# Debugging.net
KiCad netlist of a schematic drawn in Altium Designer
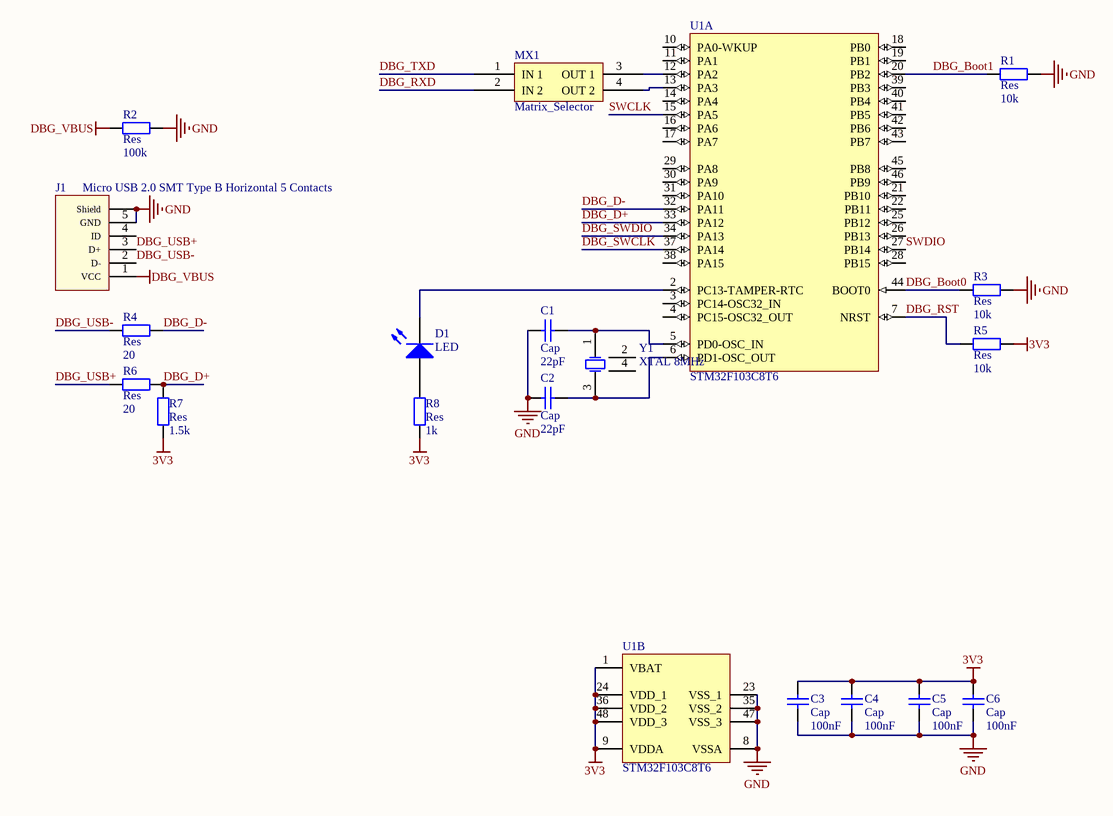
[diagram p0: Debugging.SchDoc]

(export (version "E")
  (design (tool "Eeschema 10.0.6"))
  (components
    (comp (ref "C1")
      (value "Cap")
      (footprint "C0603")
      (description "Capacitor")
      (fields (field (name "ALTIUM_VALUE") "22pF") (field (name "PUBLISHER") "Altium Limited"))
      (libsource (lib "cadLib") (part "Cap"))
    )
    (comp (ref "C2")
      (value "Cap")
      (footprint "C0603")
      (description "Capacitor")
      (fields (field (name "ALTIUM_VALUE") "22pF") (field (name "PUBLISHER") "Altium Limited"))
      (libsource (lib "cadLib") (part "Cap"))
    )
    (comp (ref "C3")
      (value "Cap")
      (footprint "C0603")
      (description "Capacitor")
      (fields (field (name "ALTIUM_VALUE") "100nF") (field (name "PUBLISHER") "Altium Limited"))
      (libsource (lib "cadLib") (part "Cap"))
    )
    (comp (ref "C4")
      (value "Cap")
      (footprint "C0603")
      (description "Capacitor")
      (fields (field (name "ALTIUM_VALUE") "100nF") (field (name "PUBLISHER") "Altium Limited"))
      (libsource (lib "cadLib") (part "Cap"))
    )
    (comp (ref "C5")
      (value "Cap")
      (footprint "C0603")
      (description "Capacitor")
      (fields (field (name "ALTIUM_VALUE") "100nF") (field (name "PUBLISHER") "Altium Limited"))
      (libsource (lib "cadLib") (part "Cap"))
    )
    (comp (ref "C6")
      (value "Cap")
      (footprint "C0603")
      (description "Capacitor")
      (fields (field (name "ALTIUM_VALUE") "100nF") (field (name "PUBLISHER") "Altium Limited"))
      (libsource (lib "cadLib") (part "Cap"))
    )
    (comp (ref "D1")
      (value "LED")
      (footprint "0805_Led")
      (description "SMD LED")
      (fields (field (name "PUBLISHER") "Altium Limited"))
      (libsource (lib "cadLib") (part "LED"))
    )
    (comp (ref "J1")
      (value "Micro USB 2.0 SMT Type B Horizontal 5 Contacts")
      (footprint "629105136821")
      (description "Micro USB 2.0 SMT Type B Horizontal 5 Contacts WR-COM")
      (fields (field (name "PART NUMBER") "629105136821") (field (name "PUBLISHER") "Wurth Elektronik"))
      (libsource (lib "USB&HDMI") (part "Micro USB 2.0 SMT Type B Horizontal 5 Contacts"))
    )
    (comp (ref "MX1")
      (value "Matrix_Selector")
      (footprint "Matrix_Selector")
      (libsource (lib "cadLib") (part "Matrix_Selector"))
    )
    (comp (ref "R1")
      (value "Res")
      (footprint "R0805")
      (description "Resistor")
      (fields (field (name "ALTIUM_VALUE") "10k") (field (name "PUBLISHER") "Altium Limited"))
      (libsource (lib "") (part "Res_1"))
    )
    (comp (ref "R2")
      (value "Res")
      (footprint "R0805")
      (description "Resistor")
      (fields (field (name "ALTIUM_VALUE") "100k") (field (name "PUBLISHER") "Altium Limited"))
      (libsource (lib "") (part "Res_2"))
    )
    (comp (ref "R3")
      (value "Res")
      (footprint "R0805")
      (description "Resistor")
      (fields (field (name "ALTIUM_VALUE") "10k") (field (name "PUBLISHER") "Altium Limited"))
      (libsource (lib "") (part "Res_1"))
    )
    (comp (ref "R4")
      (value "Res")
      (footprint "R0805")
      (description "Resistor")
      (fields (field (name "ALTIUM_VALUE") "20") (field (name "PUBLISHER") "Altium Limited"))
      (libsource (lib "") (part "Res_1"))
    )
    (comp (ref "R5")
      (value "Res")
      (footprint "R0805")
      (description "Resistor")
      (fields (field (name "ALTIUM_VALUE") "10k") (field (name "PUBLISHER") "Altium Limited"))
      (libsource (lib "") (part "Res_1"))
    )
    (comp (ref "R6")
      (value "Res")
      (footprint "R0805")
      (description "Resistor")
      (fields (field (name "ALTIUM_VALUE") "20") (field (name "PUBLISHER") "Altium Limited"))
      (libsource (lib "") (part "Res_1"))
    )
    (comp (ref "R7")
      (value "Res")
      (footprint "R0805")
      (description "Resistor")
      (fields (field (name "ALTIUM_VALUE") "1.5k") (field (name "PUBLISHER") "Altium Limited"))
      (libsource (lib "cadLib") (part "Res"))
    )
    (comp (ref "R8")
      (value "Res")
      (footprint "R0805")
      (description "Resistor")
      (fields (field (name "ALTIUM_VALUE") "1k") (field (name "PUBLISHER") "Altium Limited"))
      (libsource (lib "cadLib") (part "Res"))
    )
    (comp (ref "U1")
      (value "STM32F103C8T6")
      (footprint "STM-LQFP48_N")
      (libsource (lib "STMicroelectronics STM32 F1") (part "STM32F103C8T6"))
    )
    (comp (ref "Y1")
      (value "XTAL 8MHz")
      (footprint "SMD-3225_4P")
      (description "Crystal")
      (fields (field (name "PUBLISHER") "Altium Limited"))
      (libsource (lib "cadLib") (part "XTAL_SMD"))
    )
  )
  (nets
    (net (code "1") (name "/DBG_Boot0") (class "Default")
      (node (ref "R3") (pin "1") (pinfunction "1_1") (pintype "passive"))
      (node (ref "U1") (pin "44") (pinfunction "BOOT0_44") (pintype "input"))
    )
    (net (code "2") (name "/DBG_Boot1") (class "Default")
      (node (ref "R1") (pin "1") (pinfunction "1_1") (pintype "passive"))
      (node (ref "U1") (pin "20") (pinfunction "PB2_20") (pintype "bidirectional"))
    )
    (net (code "3") (name "/DBG_D+") (class "Default")
      (node (ref "R6") (pin "2") (pinfunction "2_2") (pintype "passive"))
      (node (ref "R7") (pin "2") (pinfunction "2_2") (pintype "passive"))
      (node (ref "U1") (pin "33") (pinfunction "PA12_33") (pintype "bidirectional"))
    )
    (net (code "4") (name "/DBG_D-") (class "Default")
      (node (ref "R4") (pin "2") (pinfunction "2_2") (pintype "passive"))
      (node (ref "U1") (pin "32") (pinfunction "PA11_32") (pintype "bidirectional"))
    )
    (net (code "5") (name "/DBG_RST") (class "Default")
      (node (ref "R5") (pin "1") (pinfunction "1_1") (pintype "passive"))
      (node (ref "U1") (pin "7") (pinfunction "NRST_7") (pintype "bidirectional"))
    )
    (net (code "6") (name "/DBG_RXD") (class "Default")
      (node (ref "MX1") (pin "2") (pinfunction "IN_2_2") (pintype "passive"))
    )
    (net (code "7") (name "/DBG_SWCLK") (class "Default")
      (node (ref "U1") (pin "37") (pinfunction "PA14_37") (pintype "bidirectional"))
    )
    (net (code "8") (name "/DBG_SWDIO") (class "Default")
      (node (ref "U1") (pin "34") (pinfunction "PA13_34") (pintype "bidirectional"))
    )
    (net (code "9") (name "/DBG_TXD") (class "Default")
      (node (ref "MX1") (pin "1") (pinfunction "IN_1_1") (pintype "passive"))
    )
    (net (code "10") (name "/DBG_USB+") (class "Default")
      (node (ref "J1") (pin "3") (pinfunction "D+_3") (pintype "passive"))
      (node (ref "R6") (pin "1") (pinfunction "1_1") (pintype "passive"))
    )
    (net (code "11") (name "/DBG_USB-") (class "Default")
      (node (ref "J1") (pin "2") (pinfunction "D-_2") (pintype "passive"))
      (node (ref "R4") (pin "1") (pinfunction "1_1") (pintype "passive"))
    )
    (net (code "12") (name "/SWCLK") (class "Default")
      (node (ref "U1") (pin "15") (pinfunction "PA5_15") (pintype "bidirectional"))
    )
    (net (code "13") (name "/SWDIO") (class "Default")
      (node (ref "U1") (pin "27") (pinfunction "PB14_27") (pintype "bidirectional"))
    )
    (net (code "14") (name "3V3") (class "Default")
      (node (ref "C3") (pin "2") (pinfunction "2_2") (pintype "passive"))
      (node (ref "C4") (pin "2") (pinfunction "2_2") (pintype "passive"))
      (node (ref "C5") (pin "2") (pinfunction "2_2") (pintype "passive"))
      (node (ref "C6") (pin "2") (pinfunction "2_2") (pintype "passive"))
      (node (ref "R5") (pin "2") (pinfunction "2_2") (pintype "passive"))
      (node (ref "R7") (pin "1") (pinfunction "1_1") (pintype "passive"))
      (node (ref "R8") (pin "1") (pinfunction "1_1") (pintype "passive"))
      (node (ref "U1") (pin "1") (pinfunction "VBAT_1") (pintype "power_in"))
      (node (ref "U1") (pin "24") (pinfunction "VDD_1_24") (pintype "power_in"))
      (node (ref "U1") (pin "36") (pinfunction "VDD_2_36") (pintype "power_in"))
      (node (ref "U1") (pin "48") (pinfunction "VDD_3_48") (pintype "power_in"))
      (node (ref "U1") (pin "9") (pinfunction "VDDA_9") (pintype "power_in"))
    )
    (net (code "15") (name "DBG_VBUS") (class "Default")
      (node (ref "J1") (pin "1") (pinfunction "VCC_1") (pintype "passive"))
      (node (ref "R2") (pin "2") (pinfunction "2_2") (pintype "passive"))
    )
    (net (code "16") (name "GND") (class "Default")
      (node (ref "C1") (pin "1") (pinfunction "1_1") (pintype "passive"))
      (node (ref "C2") (pin "1") (pinfunction "1_1") (pintype "passive"))
      (node (ref "C3") (pin "1") (pinfunction "1_1") (pintype "passive"))
      (node (ref "C4") (pin "1") (pinfunction "1_1") (pintype "passive"))
      (node (ref "C5") (pin "1") (pinfunction "1_1") (pintype "passive"))
      (node (ref "C6") (pin "1") (pinfunction "1_1") (pintype "passive"))
      (node (ref "J1") (pin "5") (pinfunction "GND_5") (pintype "passive"))
      (node (ref "J1") (pin "Shell") (pinfunction "Shield_Shell") (pintype "passive"))
      (node (ref "R1") (pin "2") (pinfunction "2_2") (pintype "passive"))
      (node (ref "R2") (pin "1") (pinfunction "1_1") (pintype "passive"))
      (node (ref "R3") (pin "2") (pinfunction "2_2") (pintype "passive"))
      (node (ref "U1") (pin "23") (pinfunction "VSS_1_23") (pintype "power_in"))
      (node (ref "U1") (pin "35") (pinfunction "VSS_2_35") (pintype "power_in"))
      (node (ref "U1") (pin "47") (pinfunction "VSS_3_47") (pintype "power_in"))
      (node (ref "U1") (pin "8") (pinfunction "VSSA_8") (pintype "power_in"))
    )
    (net (code "17") (name "Net-(D1-A)") (class "Default")
      (node (ref "D1") (pin "2") (pinfunction "A_2") (pintype "passive"))
      (node (ref "R8") (pin "2") (pinfunction "2_2") (pintype "passive"))
    )
    (net (code "18") (name "Net-(D1-K)") (class "Default")
      (node (ref "D1") (pin "1") (pinfunction "K_1") (pintype "passive"))
      (node (ref "U1") (pin "2") (pinfunction "PC13-TAMPER-RTC_2") (pintype "bidirectional"))
    )
    (net (code "19") (name "Net-(MX1-OUT_1)") (class "Default")
      (node (ref "MX1") (pin "3") (pinfunction "OUT_1_3") (pintype "passive"))
      (node (ref "U1") (pin "12") (pinfunction "PA2_12") (pintype "bidirectional"))
    )
    (net (code "20") (name "Net-(MX1-OUT_2)") (class "Default")
      (node (ref "MX1") (pin "4") (pinfunction "OUT_2_4") (pintype "passive"))
      (node (ref "U1") (pin "13") (pinfunction "PA3_13") (pintype "bidirectional"))
    )
    (net (code "21") (name "Net-(U1A-PD0-OSC_IN)") (class "Default")
      (node (ref "C1") (pin "2") (pinfunction "2_2") (pintype "passive"))
      (node (ref "U1") (pin "5") (pinfunction "PD0-OSC_IN_5") (pintype "bidirectional"))
      (node (ref "Y1") (pin "1") (pinfunction "OSC1_1") (pintype "passive"))
    )
    (net (code "22") (name "Net-(U1A-PD1-OSC_OUT)") (class "Default")
      (node (ref "C2") (pin "2") (pinfunction "2_2") (pintype "passive"))
      (node (ref "U1") (pin "6") (pinfunction "PD1-OSC_OUT_6") (pintype "bidirectional"))
      (node (ref "Y1") (pin "3") (pinfunction "OSC2_3") (pintype "passive"))
    )
    (net (code "23") (name "unconnected-(J1-ID-Pad4)") (class "Default")
      (node (ref "J1") (pin "4") (pinfunction "ID_4") (pintype "passive"))
    )
    (net (code "24") (name "unconnected-(U1A-PA0-WKUP-Pad10)") (class "Default")
      (node (ref "U1") (pin "10") (pinfunction "PA0-WKUP_10") (pintype "bidirectional"))
    )
    (net (code "25") (name "unconnected-(U1A-PA1-Pad11)") (class "Default")
      (node (ref "U1") (pin "11") (pinfunction "PA1_11") (pintype "bidirectional"))
    )
    (net (code "26") (name "unconnected-(U1A-PA4-Pad14)") (class "Default")
      (node (ref "U1") (pin "14") (pinfunction "PA4_14") (pintype "bidirectional"))
    )
    (net (code "27") (name "unconnected-(U1A-PA6-Pad16)") (class "Default")
      (node (ref "U1") (pin "16") (pinfunction "PA6_16") (pintype "bidirectional"))
    )
    (net (code "28") (name "unconnected-(U1A-PA7-Pad17)") (class "Default")
      (node (ref "U1") (pin "17") (pinfunction "PA7_17") (pintype "bidirectional"))
    )
    (net (code "29") (name "unconnected-(U1A-PA8-Pad29)") (class "Default")
      (node (ref "U1") (pin "29") (pinfunction "PA8_29") (pintype "bidirectional"))
    )
    (net (code "30") (name "unconnected-(U1A-PA9-Pad30)") (class "Default")
      (node (ref "U1") (pin "30") (pinfunction "PA9_30") (pintype "bidirectional"))
    )
    (net (code "31") (name "unconnected-(U1A-PA10-Pad31)") (class "Default")
      (node (ref "U1") (pin "31") (pinfunction "PA10_31") (pintype "bidirectional"))
    )
    (net (code "32") (name "unconnected-(U1A-PA15-Pad38)") (class "Default")
      (node (ref "U1") (pin "38") (pinfunction "PA15_38") (pintype "bidirectional"))
    )
    (net (code "33") (name "unconnected-(U1A-PB0-Pad18)") (class "Default")
      (node (ref "U1") (pin "18") (pinfunction "PB0_18") (pintype "bidirectional"))
    )
    (net (code "34") (name "unconnected-(U1A-PB1-Pad19)") (class "Default")
      (node (ref "U1") (pin "19") (pinfunction "PB1_19") (pintype "bidirectional"))
    )
    (net (code "35") (name "unconnected-(U1A-PB3-Pad39)") (class "Default")
      (node (ref "U1") (pin "39") (pinfunction "PB3_39") (pintype "bidirectional"))
    )
    (net (code "36") (name "unconnected-(U1A-PB4-Pad40)") (class "Default")
      (node (ref "U1") (pin "40") (pinfunction "PB4_40") (pintype "bidirectional"))
    )
    (net (code "37") (name "unconnected-(U1A-PB5-Pad41)") (class "Default")
      (node (ref "U1") (pin "41") (pinfunction "PB5_41") (pintype "bidirectional"))
    )
    (net (code "38") (name "unconnected-(U1A-PB6-Pad42)") (class "Default")
      (node (ref "U1") (pin "42") (pinfunction "PB6_42") (pintype "bidirectional"))
    )
    (net (code "39") (name "unconnected-(U1A-PB7-Pad43)") (class "Default")
      (node (ref "U1") (pin "43") (pinfunction "PB7_43") (pintype "bidirectional"))
    )
    (net (code "40") (name "unconnected-(U1A-PB8-Pad45)") (class "Default")
      (node (ref "U1") (pin "45") (pinfunction "PB8_45") (pintype "bidirectional"))
    )
    (net (code "41") (name "unconnected-(U1A-PB9-Pad46)") (class "Default")
      (node (ref "U1") (pin "46") (pinfunction "PB9_46") (pintype "bidirectional"))
    )
    (net (code "42") (name "unconnected-(U1A-PB10-Pad21)") (class "Default")
      (node (ref "U1") (pin "21") (pinfunction "PB10_21") (pintype "bidirectional"))
    )
    (net (code "43") (name "unconnected-(U1A-PB11-Pad22)") (class "Default")
      (node (ref "U1") (pin "22") (pinfunction "PB11_22") (pintype "bidirectional"))
    )
    (net (code "44") (name "unconnected-(U1A-PB12-Pad25)") (class "Default")
      (node (ref "U1") (pin "25") (pinfunction "PB12_25") (pintype "bidirectional"))
    )
    (net (code "45") (name "unconnected-(U1A-PB13-Pad26)") (class "Default")
      (node (ref "U1") (pin "26") (pinfunction "PB13_26") (pintype "bidirectional"))
    )
    (net (code "46") (name "unconnected-(U1A-PB15-Pad28)") (class "Default")
      (node (ref "U1") (pin "28") (pinfunction "PB15_28") (pintype "bidirectional"))
    )
    (net (code "47") (name "unconnected-(U1A-PC14-OSC32_IN-Pad3)") (class "Default")
      (node (ref "U1") (pin "3") (pinfunction "PC14-OSC32_IN_3") (pintype "bidirectional"))
    )
    (net (code "48") (name "unconnected-(U1A-PC15-OSC32_OUT-Pad4)") (class "Default")
      (node (ref "U1") (pin "4") (pinfunction "PC15-OSC32_OUT_4") (pintype "bidirectional"))
    )
    (net (code "49") (name "unconnected-(Y1-OSC1-Pad2)") (class "Default")
      (node (ref "Y1") (pin "2") (pinfunction "OSC1_2") (pintype "passive"))
    )
    (net (code "50") (name "unconnected-(Y1-OSC1-Pad4)") (class "Default")
      (node (ref "Y1") (pin "4") (pinfunction "OSC1_4") (pintype "passive"))
    )
  )
)
